# Main.net
KiCad netlist of a schematic drawn in Altium Designer
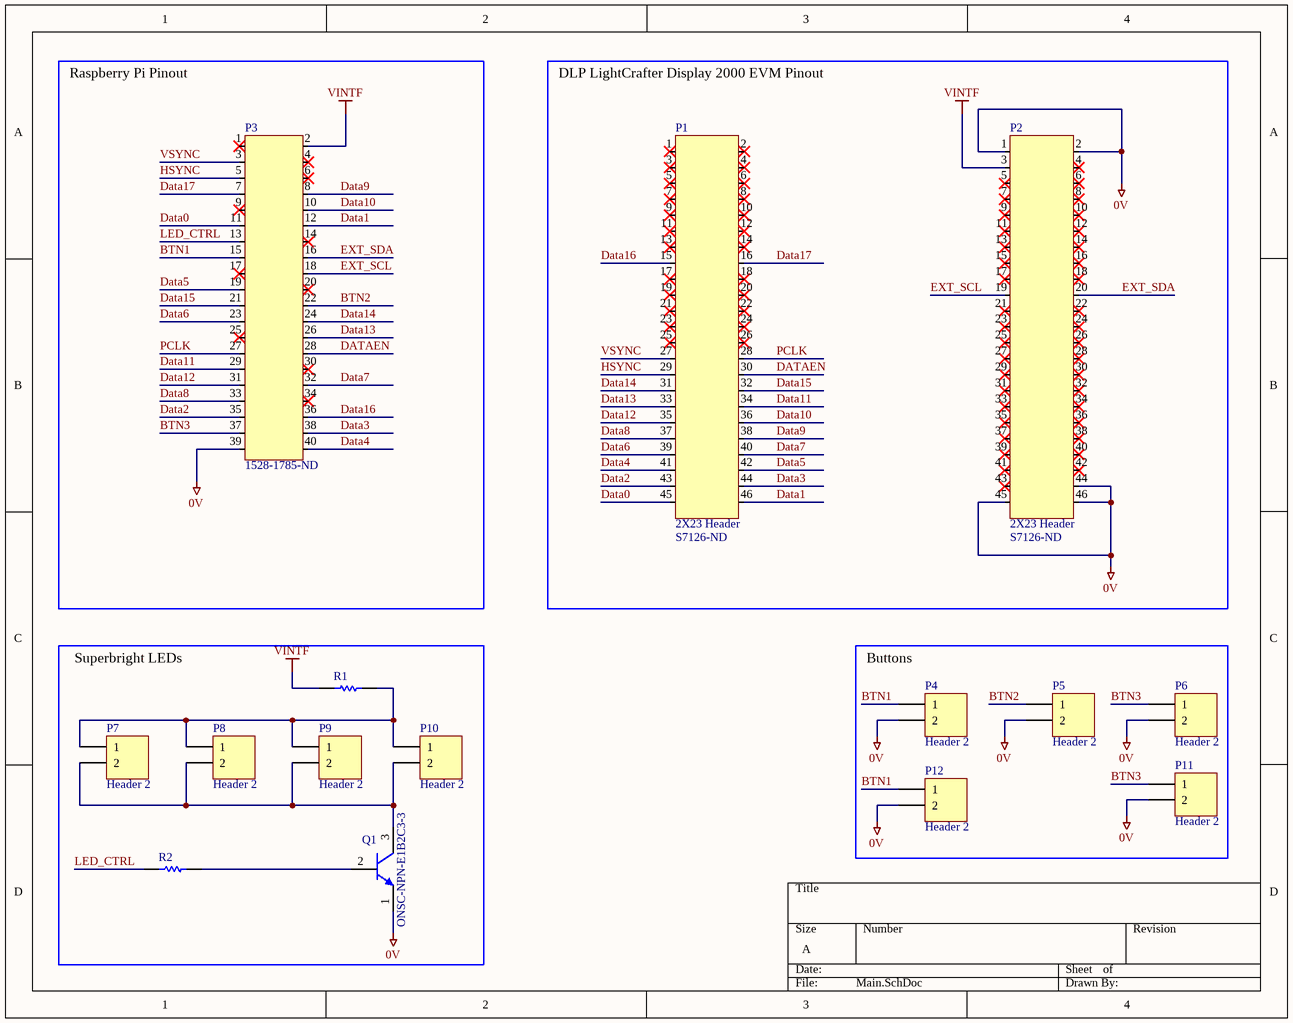
[diagram p0: Main.SchDoc]

(export (version "E")
  (design (tool "Eeschema 10.0.6"))
  (components
    (comp (ref "P1")
      (value "2X23 Header")
      (footprint "2X23 hEADER")
      (fields
        (field (name "MANUFACTURER") "Sullins")
        (field (name "MANUFACTURER PART NUMBER") "PPPC232LFBN-RC")
        (field (name "SUPPLIER PART NUMBER 1") "S7126-ND")
      )
      (libsource (lib "BikeHUD") (part "PPPC232LFBN-RC"))
    )
    (comp (ref "P2")
      (value "2X23 Header")
      (footprint "2X23 hEADER")
      (fields
        (field (name "MANUFACTURER") "Sullins")
        (field (name "MANUFACTURER PART NUMBER") "PPPC232LFBN-RC")
        (field (name "SUPPLIER PART NUMBER 1") "S7126-ND")
      )
      (libsource (lib "BikeHUD") (part "PPPC232LFBN-RC"))
    )
    (comp (ref "P3")
      (value "2x20 Header")
      (footprint "2222")
      (description "GPIO FEMALE HEADER RASPBERRY PI")
      (fields
        (field (name "MANUFACTURER") "Adafruit Industries")
        (field (name "MANUFACTURER PART NUMBER") "2222")
        (field (name "SUPPLIER PART NUMBER 1") "1528-1785-ND")
      )
      (libsource (lib "BikeHUD") (part "2222"))
    )
    (comp (ref "P4")
      (value "Header 2")
      (footprint "HDR1X2")
      (description "Header, 2-Pin")
      (fields (field (name "PUBLISHER") "Altium Limited"))
      (libsource (lib "BikeHUD") (part "Header 2"))
    )
    (comp (ref "P5")
      (value "Header 2")
      (footprint "HDR1X2")
      (description "Header, 2-Pin")
      (fields (field (name "PUBLISHER") "Altium Limited"))
      (libsource (lib "BikeHUD") (part "Header 2"))
    )
    (comp (ref "P6")
      (value "Header 2")
      (footprint "HDR1X2")
      (description "Header, 2-Pin")
      (fields (field (name "PUBLISHER") "Altium Limited"))
      (libsource (lib "BikeHUD") (part "Header 2"))
    )
    (comp (ref "P7")
      (value "Header 2")
      (footprint "HDR1X2")
      (description "Header, 2-Pin")
      (fields (field (name "PUBLISHER") "Altium Limited"))
      (libsource (lib "BikeHUD") (part "Header 2"))
    )
    (comp (ref "P8")
      (value "Header 2")
      (footprint "HDR1X2")
      (description "Header, 2-Pin")
      (fields (field (name "PUBLISHER") "Altium Limited"))
      (libsource (lib "BikeHUD") (part "Header 2"))
    )
    (comp (ref "P9")
      (value "Header 2")
      (footprint "HDR1X2")
      (description "Header, 2-Pin")
      (fields (field (name "PUBLISHER") "Altium Limited"))
      (libsource (lib "BikeHUD") (part "Header 2"))
    )
    (comp (ref "P10")
      (value "Header 2")
      (footprint "HDR1X2")
      (description "Header, 2-Pin")
      (fields (field (name "PUBLISHER") "Altium Limited"))
      (libsource (lib "BikeHUD") (part "Header 2"))
    )
    (comp (ref "P11")
      (value "Header 2")
      (footprint "HDR1X2")
      (description "Header, 2-Pin")
      (fields (field (name "PUBLISHER") "Altium Limited"))
      (libsource (lib "BikeHUD") (part "Header 2"))
    )
    (comp (ref "P12")
      (value "Header 2")
      (footprint "HDR1X2")
      (description "Header, 2-Pin")
      (fields (field (name "PUBLISHER") "Altium Limited"))
      (libsource (lib "BikeHUD") (part "Header 2"))
    )
    (comp (ref "Q1")
      (value "ONSC-NPN-E1B2C3-3")
      (footprint "ONSC-TO-92-3-29-11")
      (libsource (lib "BikeHUD") (part "ONSC-NPN-E1B2C3-3"))
    )
    (comp (ref "R1")
      (value "Res1")
      (footprint "AXIAL-0.3")
      (description "Resistor")
      (fields (field (name "PUBLISHER") "Altium Limited"))
      (libsource (lib "BikeHUD") (part "Res1"))
    )
    (comp (ref "R2")
      (value "Res1")
      (footprint "AXIAL-0.3")
      (description "Resistor")
      (fields (field (name "PUBLISHER") "Altium Limited"))
      (libsource (lib "BikeHUD") (part "Res1"))
    )
  )
  (nets
    (net (code "1") (name "/BTN1") (class "Default")
      (node (ref "P12") (pin "1") (pinfunction "1_1") (pintype "passive"))
      (node (ref "P3") (pin "15") (pinfunction "15_15") (pintype "passive"))
      (node (ref "P4") (pin "1") (pinfunction "1_1") (pintype "passive"))
    )
    (net (code "2") (name "/BTN2") (class "Default")
      (node (ref "P3") (pin "22") (pinfunction "22_22") (pintype "passive"))
      (node (ref "P5") (pin "1") (pinfunction "1_1") (pintype "passive"))
    )
    (net (code "3") (name "/BTN3") (class "Default")
      (node (ref "P11") (pin "1") (pinfunction "1_1") (pintype "passive"))
      (node (ref "P3") (pin "37") (pinfunction "37_37") (pintype "passive"))
      (node (ref "P6") (pin "1") (pinfunction "1_1") (pintype "passive"))
    )
    (net (code "4") (name "/DATAEN") (class "Default")
      (node (ref "P1") (pin "30") (pinfunction "30_30") (pintype "passive"))
      (node (ref "P3") (pin "28") (pinfunction "28_28") (pintype "passive"))
    )
    (net (code "5") (name "/Data0") (class "Default")
      (node (ref "P1") (pin "45") (pinfunction "45_45") (pintype "passive"))
      (node (ref "P3") (pin "11") (pinfunction "11_11") (pintype "passive"))
    )
    (net (code "6") (name "/Data1") (class "Default")
      (node (ref "P1") (pin "46") (pinfunction "46_46") (pintype "passive"))
      (node (ref "P3") (pin "12") (pinfunction "12_12") (pintype "passive"))
    )
    (net (code "7") (name "/Data2") (class "Default")
      (node (ref "P1") (pin "43") (pinfunction "43_43") (pintype "passive"))
      (node (ref "P3") (pin "35") (pinfunction "35_35") (pintype "passive"))
    )
    (net (code "8") (name "/Data3") (class "Default")
      (node (ref "P1") (pin "44") (pinfunction "44_44") (pintype "passive"))
      (node (ref "P3") (pin "38") (pinfunction "38_38") (pintype "passive"))
    )
    (net (code "9") (name "/Data4") (class "Default")
      (node (ref "P1") (pin "41") (pinfunction "41_41") (pintype "passive"))
      (node (ref "P3") (pin "40") (pinfunction "40_40") (pintype "passive"))
    )
    (net (code "10") (name "/Data5") (class "Default")
      (node (ref "P1") (pin "42") (pinfunction "42_42") (pintype "passive"))
      (node (ref "P3") (pin "19") (pinfunction "19_19") (pintype "passive"))
    )
    (net (code "11") (name "/Data6") (class "Default")
      (node (ref "P1") (pin "39") (pinfunction "39_39") (pintype "passive"))
      (node (ref "P3") (pin "23") (pinfunction "23_23") (pintype "passive"))
    )
    (net (code "12") (name "/Data7") (class "Default")
      (node (ref "P1") (pin "40") (pinfunction "40_40") (pintype "passive"))
      (node (ref "P3") (pin "32") (pinfunction "32_32") (pintype "passive"))
    )
    (net (code "13") (name "/Data8") (class "Default")
      (node (ref "P1") (pin "37") (pinfunction "37_37") (pintype "passive"))
      (node (ref "P3") (pin "33") (pinfunction "33_33") (pintype "passive"))
    )
    (net (code "14") (name "/Data9") (class "Default")
      (node (ref "P1") (pin "38") (pinfunction "38_38") (pintype "passive"))
      (node (ref "P3") (pin "8") (pinfunction "8_8") (pintype "passive"))
    )
    (net (code "15") (name "/Data10") (class "Default")
      (node (ref "P1") (pin "36") (pinfunction "36_36") (pintype "passive"))
      (node (ref "P3") (pin "10") (pinfunction "10_10") (pintype "passive"))
    )
    (net (code "16") (name "/Data11") (class "Default")
      (node (ref "P1") (pin "34") (pinfunction "34_34") (pintype "passive"))
      (node (ref "P3") (pin "29") (pinfunction "29_29") (pintype "passive"))
    )
    (net (code "17") (name "/Data12") (class "Default")
      (node (ref "P1") (pin "35") (pinfunction "35_35") (pintype "passive"))
      (node (ref "P3") (pin "31") (pinfunction "31_31") (pintype "passive"))
    )
    (net (code "18") (name "/Data13") (class "Default")
      (node (ref "P1") (pin "33") (pinfunction "33_33") (pintype "passive"))
      (node (ref "P3") (pin "26") (pinfunction "26_26") (pintype "passive"))
    )
    (net (code "19") (name "/Data14") (class "Default")
      (node (ref "P1") (pin "31") (pinfunction "31_31") (pintype "passive"))
      (node (ref "P3") (pin "24") (pinfunction "24_24") (pintype "passive"))
    )
    (net (code "20") (name "/Data15") (class "Default")
      (node (ref "P1") (pin "32") (pinfunction "32_32") (pintype "passive"))
      (node (ref "P3") (pin "21") (pinfunction "21_21") (pintype "passive"))
    )
    (net (code "21") (name "/Data16") (class "Default")
      (node (ref "P1") (pin "15") (pinfunction "15_15") (pintype "passive"))
      (node (ref "P3") (pin "36") (pinfunction "36_36") (pintype "passive"))
    )
    (net (code "22") (name "/Data17") (class "Default")
      (node (ref "P1") (pin "16") (pinfunction "16_16") (pintype "passive"))
      (node (ref "P3") (pin "7") (pinfunction "7_7") (pintype "passive"))
    )
    (net (code "23") (name "/EXT_SCL") (class "Default")
      (node (ref "P2") (pin "19") (pinfunction "19_19") (pintype "passive"))
      (node (ref "P3") (pin "18") (pinfunction "_18_18") (pintype "passive"))
    )
    (net (code "24") (name "/EXT_SDA") (class "Default")
      (node (ref "P2") (pin "20") (pinfunction "20_20") (pintype "passive"))
      (node (ref "P3") (pin "16") (pinfunction "16_16") (pintype "passive"))
    )
    (net (code "25") (name "/HSYNC") (class "Default")
      (node (ref "P1") (pin "29") (pinfunction "29_29") (pintype "passive"))
      (node (ref "P3") (pin "5") (pinfunction "5_5") (pintype "passive"))
    )
    (net (code "26") (name "/LED_CTRL") (class "Default")
      (node (ref "P3") (pin "13") (pinfunction "13_13") (pintype "passive"))
      (node (ref "R2") (pin "1") (pinfunction "1_1") (pintype "passive"))
    )
    (net (code "27") (name "/PCLK") (class "Default")
      (node (ref "P1") (pin "28") (pinfunction "28_28") (pintype "passive"))
      (node (ref "P3") (pin "27") (pinfunction "27_27") (pintype "passive"))
    )
    (net (code "28") (name "/VSYNC") (class "Default")
      (node (ref "P1") (pin "27") (pinfunction "27_27") (pintype "passive"))
      (node (ref "P3") (pin "3") (pinfunction "3_3") (pintype "passive"))
    )
    (net (code "29") (name "0V") (class "Default")
      (node (ref "P11") (pin "2") (pinfunction "2_2") (pintype "passive"))
      (node (ref "P12") (pin "2") (pinfunction "2_2") (pintype "passive"))
      (node (ref "P2") (pin "1") (pinfunction "1_1") (pintype "passive"))
      (node (ref "P2") (pin "2") (pinfunction "2_2") (pintype "passive"))
      (node (ref "P2") (pin "44") (pinfunction "44_44") (pintype "passive"))
      (node (ref "P2") (pin "45") (pinfunction "45_45") (pintype "passive"))
      (node (ref "P2") (pin "46") (pinfunction "46_46") (pintype "passive"))
      (node (ref "P3") (pin "39") (pinfunction "39_39") (pintype "passive"))
      (node (ref "P4") (pin "2") (pinfunction "2_2") (pintype "passive"))
      (node (ref "P5") (pin "2") (pinfunction "2_2") (pintype "passive"))
      (node (ref "P6") (pin "2") (pinfunction "2_2") (pintype "passive"))
      (node (ref "Q1") (pin "1") (pinfunction "E_1") (pintype "passive"))
    )
    (net (code "30") (name "Net-(P10-Pad1)") (class "Default")
      (node (ref "P10") (pin "1") (pinfunction "1_1") (pintype "passive"))
      (node (ref "P7") (pin "1") (pinfunction "1_1") (pintype "passive"))
      (node (ref "P8") (pin "1") (pinfunction "1_1") (pintype "passive"))
      (node (ref "P9") (pin "1") (pinfunction "1_1") (pintype "passive"))
      (node (ref "R1") (pin "2") (pinfunction "2_2") (pintype "passive"))
    )
    (net (code "31") (name "Net-(Q1-B)") (class "Default")
      (node (ref "Q1") (pin "2") (pinfunction "B_2") (pintype "passive"))
      (node (ref "R2") (pin "2") (pinfunction "2_2") (pintype "passive"))
    )
    (net (code "32") (name "Net-(Q1-C)") (class "Default")
      (node (ref "P10") (pin "2") (pinfunction "2_2") (pintype "passive"))
      (node (ref "P7") (pin "2") (pinfunction "2_2") (pintype "passive"))
      (node (ref "P8") (pin "2") (pinfunction "2_2") (pintype "passive"))
      (node (ref "P9") (pin "2") (pinfunction "2_2") (pintype "passive"))
      (node (ref "Q1") (pin "3") (pinfunction "C_3") (pintype "passive"))
    )
    (net (code "33") (name "VINTF") (class "Default")
      (node (ref "P2") (pin "3") (pinfunction "3_3") (pintype "passive"))
      (node (ref "P3") (pin "2") (pinfunction "2_2") (pintype "passive"))
      (node (ref "R1") (pin "1") (pinfunction "1_1") (pintype "passive"))
    )
    (net (code "34") (name "unconnected-(P1-Pad1)") (class "Default")
      (node (ref "P1") (pin "1") (pinfunction "1_1") (pintype "passive+no_connect"))
    )
    (net (code "35") (name "unconnected-(P1-Pad2)") (class "Default")
      (node (ref "P1") (pin "2") (pinfunction "2_2") (pintype "passive+no_connect"))
    )
    (net (code "36") (name "unconnected-(P1-Pad3)") (class "Default")
      (node (ref "P1") (pin "3") (pinfunction "3_3") (pintype "passive+no_connect"))
    )
    (net (code "37") (name "unconnected-(P1-Pad4)") (class "Default")
      (node (ref "P1") (pin "4") (pinfunction "4_4") (pintype "passive+no_connect"))
    )
    (net (code "38") (name "unconnected-(P1-Pad5)") (class "Default")
      (node (ref "P1") (pin "5") (pinfunction "5_5") (pintype "passive+no_connect"))
    )
    (net (code "39") (name "unconnected-(P1-Pad6)") (class "Default")
      (node (ref "P1") (pin "6") (pinfunction "6_6") (pintype "passive+no_connect"))
    )
    (net (code "40") (name "unconnected-(P1-Pad7)") (class "Default")
      (node (ref "P1") (pin "7") (pinfunction "7_7") (pintype "passive+no_connect"))
    )
    (net (code "41") (name "unconnected-(P1-Pad8)") (class "Default")
      (node (ref "P1") (pin "8") (pinfunction "8_8") (pintype "passive+no_connect"))
    )
    (net (code "42") (name "unconnected-(P1-Pad9)") (class "Default")
      (node (ref "P1") (pin "9") (pinfunction "9_9") (pintype "passive+no_connect"))
    )
    (net (code "43") (name "unconnected-(P1-Pad10)") (class "Default")
      (node (ref "P1") (pin "10") (pinfunction "10_10") (pintype "passive+no_connect"))
    )
    (net (code "44") (name "unconnected-(P1-Pad11)") (class "Default")
      (node (ref "P1") (pin "11") (pinfunction "11_11") (pintype "passive+no_connect"))
    )
    (net (code "45") (name "unconnected-(P1-Pad12)") (class "Default")
      (node (ref "P1") (pin "12") (pinfunction "12_12") (pintype "passive+no_connect"))
    )
    (net (code "46") (name "unconnected-(P1-Pad13)") (class "Default")
      (node (ref "P1") (pin "13") (pinfunction "13_13") (pintype "passive+no_connect"))
    )
    (net (code "47") (name "unconnected-(P1-Pad14)") (class "Default")
      (node (ref "P1") (pin "14") (pinfunction "14_14") (pintype "passive+no_connect"))
    )
    (net (code "48") (name "unconnected-(P1-Pad17)") (class "Default")
      (node (ref "P1") (pin "17") (pinfunction "17_17") (pintype "passive+no_connect"))
    )
    (net (code "49") (name "unconnected-(P1-Pad18)") (class "Default")
      (node (ref "P1") (pin "18") (pinfunction "18_18") (pintype "passive+no_connect"))
    )
    (net (code "50") (name "unconnected-(P1-Pad19)") (class "Default")
      (node (ref "P1") (pin "19") (pinfunction "19_19") (pintype "passive+no_connect"))
    )
    (net (code "51") (name "unconnected-(P1-Pad20)") (class "Default")
      (node (ref "P1") (pin "20") (pinfunction "20_20") (pintype "passive+no_connect"))
    )
    (net (code "52") (name "unconnected-(P1-Pad21)") (class "Default")
      (node (ref "P1") (pin "21") (pinfunction "21_21") (pintype "passive+no_connect"))
    )
    (net (code "53") (name "unconnected-(P1-Pad22)") (class "Default")
      (node (ref "P1") (pin "22") (pinfunction "22_22") (pintype "passive+no_connect"))
    )
    (net (code "54") (name "unconnected-(P1-Pad23)") (class "Default")
      (node (ref "P1") (pin "23") (pinfunction "23_23") (pintype "passive+no_connect"))
    )
    (net (code "55") (name "unconnected-(P1-Pad24)") (class "Default")
      (node (ref "P1") (pin "24") (pinfunction "24_24") (pintype "passive+no_connect"))
    )
    (net (code "56") (name "unconnected-(P1-Pad25)") (class "Default")
      (node (ref "P1") (pin "25") (pinfunction "25_25") (pintype "passive+no_connect"))
    )
    (net (code "57") (name "unconnected-(P1-Pad26)") (class "Default")
      (node (ref "P1") (pin "26") (pinfunction "26_26") (pintype "passive+no_connect"))
    )
    (net (code "58") (name "unconnected-(P2-Pad4)") (class "Default")
      (node (ref "P2") (pin "4") (pinfunction "4_4") (pintype "passive+no_connect"))
    )
    (net (code "59") (name "unconnected-(P2-Pad5)") (class "Default")
      (node (ref "P2") (pin "5") (pinfunction "5_5") (pintype "passive+no_connect"))
    )
    (net (code "60") (name "unconnected-(P2-Pad6)") (class "Default")
      (node (ref "P2") (pin "6") (pinfunction "6_6") (pintype "passive+no_connect"))
    )
    (net (code "61") (name "unconnected-(P2-Pad7)") (class "Default")
      (node (ref "P2") (pin "7") (pinfunction "7_7") (pintype "passive+no_connect"))
    )
    (net (code "62") (name "unconnected-(P2-Pad8)") (class "Default")
      (node (ref "P2") (pin "8") (pinfunction "8_8") (pintype "passive+no_connect"))
    )
    (net (code "63") (name "unconnected-(P2-Pad9)") (class "Default")
      (node (ref "P2") (pin "9") (pinfunction "9_9") (pintype "passive+no_connect"))
    )
    (net (code "64") (name "unconnected-(P2-Pad10)") (class "Default")
      (node (ref "P2") (pin "10") (pinfunction "10_10") (pintype "passive+no_connect"))
    )
    (net (code "65") (name "unconnected-(P2-Pad11)") (class "Default")
      (node (ref "P2") (pin "11") (pinfunction "11_11") (pintype "passive+no_connect"))
    )
    (net (code "66") (name "unconnected-(P2-Pad12)") (class "Default")
      (node (ref "P2") (pin "12") (pinfunction "12_12") (pintype "passive+no_connect"))
    )
    (net (code "67") (name "unconnected-(P2-Pad13)") (class "Default")
      (node (ref "P2") (pin "13") (pinfunction "13_13") (pintype "passive+no_connect"))
    )
    (net (code "68") (name "unconnected-(P2-Pad14)") (class "Default")
      (node (ref "P2") (pin "14") (pinfunction "14_14") (pintype "passive+no_connect"))
    )
    (net (code "69") (name "unconnected-(P2-Pad15)") (class "Default")
      (node (ref "P2") (pin "15") (pinfunction "15_15") (pintype "passive+no_connect"))
    )
    (net (code "70") (name "unconnected-(P2-Pad16)") (class "Default")
      (node (ref "P2") (pin "16") (pinfunction "16_16") (pintype "passive+no_connect"))
    )
    (net (code "71") (name "unconnected-(P2-Pad17)") (class "Default")
      (node (ref "P2") (pin "17") (pinfunction "17_17") (pintype "passive+no_connect"))
    )
    (net (code "72") (name "unconnected-(P2-Pad18)") (class "Default")
      (node (ref "P2") (pin "18") (pinfunction "18_18") (pintype "passive+no_connect"))
    )
    (net (code "73") (name "unconnected-(P2-Pad21)") (class "Default")
      (node (ref "P2") (pin "21") (pinfunction "21_21") (pintype "passive+no_connect"))
    )
    (net (code "74") (name "unconnected-(P2-Pad22)") (class "Default")
      (node (ref "P2") (pin "22") (pinfunction "22_22") (pintype "passive+no_connect"))
    )
    (net (code "75") (name "unconnected-(P2-Pad23)") (class "Default")
      (node (ref "P2") (pin "23") (pinfunction "23_23") (pintype "passive+no_connect"))
    )
    (net (code "76") (name "unconnected-(P2-Pad24)") (class "Default")
      (node (ref "P2") (pin "24") (pinfunction "24_24") (pintype "passive+no_connect"))
    )
    (net (code "77") (name "unconnected-(P2-Pad25)") (class "Default")
      (node (ref "P2") (pin "25") (pinfunction "25_25") (pintype "passive+no_connect"))
    )
    (net (code "78") (name "unconnected-(P2-Pad26)") (class "Default")
      (node (ref "P2") (pin "26") (pinfunction "26_26") (pintype "passive+no_connect"))
    )
    (net (code "79") (name "unconnected-(P2-Pad27)") (class "Default")
      (node (ref "P2") (pin "27") (pinfunction "27_27") (pintype "passive+no_connect"))
    )
    (net (code "80") (name "unconnected-(P2-Pad28)") (class "Default")
      (node (ref "P2") (pin "28") (pinfunction "28_28") (pintype "passive+no_connect"))
    )
    (net (code "81") (name "unconnected-(P2-Pad29)") (class "Default")
      (node (ref "P2") (pin "29") (pinfunction "29_29") (pintype "passive+no_connect"))
    )
    (net (code "82") (name "unconnected-(P2-Pad30)") (class "Default")
      (node (ref "P2") (pin "30") (pinfunction "30_30") (pintype "passive+no_connect"))
    )
    (net (code "83") (name "unconnected-(P2-Pad31)") (class "Default")
      (node (ref "P2") (pin "31") (pinfunction "31_31") (pintype "passive+no_connect"))
    )
    (net (code "84") (name "unconnected-(P2-Pad32)") (class "Default")
      (node (ref "P2") (pin "32") (pinfunction "32_32") (pintype "passive+no_connect"))
    )
    (net (code "85") (name "unconnected-(P2-Pad33)") (class "Default")
      (node (ref "P2") (pin "33") (pinfunction "33_33") (pintype "passive+no_connect"))
    )
    (net (code "86") (name "unconnected-(P2-Pad34)") (class "Default")
      (node (ref "P2") (pin "34") (pinfunction "34_34") (pintype "passive+no_connect"))
    )
    (net (code "87") (name "unconnected-(P2-Pad35)") (class "Default")
      (node (ref "P2") (pin "35") (pinfunction "35_35") (pintype "passive+no_connect"))
    )
    (net (code "88") (name "unconnected-(P2-Pad36)") (class "Default")
      (node (ref "P2") (pin "36") (pinfunction "36_36") (pintype "passive+no_connect"))
    )
    (net (code "89") (name "unconnected-(P2-Pad37)") (class "Default")
      (node (ref "P2") (pin "37") (pinfunction "37_37") (pintype "passive+no_connect"))
    )
    (net (code "90") (name "unconnected-(P2-Pad38)") (class "Default")
      (node (ref "P2") (pin "38") (pinfunction "38_38") (pintype "passive+no_connect"))
    )
    (net (code "91") (name "unconnected-(P2-Pad39)") (class "Default")
      (node (ref "P2") (pin "39") (pinfunction "39_39") (pintype "passive+no_connect"))
    )
    (net (code "92") (name "unconnected-(P2-Pad40)") (class "Default")
      (node (ref "P2") (pin "40") (pinfunction "40_40") (pintype "passive+no_connect"))
    )
    (net (code "93") (name "unconnected-(P2-Pad41)") (class "Default")
      (node (ref "P2") (pin "41") (pinfunction "41_41") (pintype "passive+no_connect"))
    )
    (net (code "94") (name "unconnected-(P2-Pad42)") (class "Default")
      (node (ref "P2") (pin "42") (pinfunction "42_42") (pintype "passive+no_connect"))
    )
    (net (code "95") (name "unconnected-(P2-Pad43)") (class "Default")
      (node (ref "P2") (pin "43") (pinfunction "43_43") (pintype "passive+no_connect"))
    )
    (net (code "96") (name "unconnected-(P3-Pad1)") (class "Default")
      (node (ref "P3") (pin "1") (pinfunction "1_1") (pintype "passive+no_connect"))
    )
    (net (code "97") (name "unconnected-(P3-Pad4)") (class "Default")
      (node (ref "P3") (pin "4") (pinfunction "4_4") (pintype "passive+no_connect"))
    )
    (net (code "98") (name "unconnected-(P3-Pad6)") (class "Default")
      (node (ref "P3") (pin "6") (pinfunction "6_6") (pintype "passive+no_connect"))
    )
    (net (code "99") (name "unconnected-(P3-Pad9)") (class "Default")
      (node (ref "P3") (pin "9") (pinfunction "9_9") (pintype "passive+no_connect"))
    )
    (net (code "100") (name "unconnected-(P3-Pad14)") (class "Default")
      (node (ref "P3") (pin "14") (pinfunction "14_14") (pintype "passive+no_connect"))
    )
    (net (code "101") (name "unconnected-(P3-Pad17)") (class "Default")
      (node (ref "P3") (pin "17") (pinfunction "17_17") (pintype "passive+no_connect"))
    )
    (net (code "102") (name "unconnected-(P3-Pad20)") (class "Default")
      (node (ref "P3") (pin "20") (pinfunction "20_20") (pintype "passive+no_connect"))
    )
    (net (code "103") (name "unconnected-(P3-Pad25)") (class "Default")
      (node (ref "P3") (pin "25") (pinfunction "25_25") (pintype "passive+no_connect"))
    )
    (net (code "104") (name "unconnected-(P3-Pad30)") (class "Default")
      (node (ref "P3") (pin "30") (pinfunction "30_30") (pintype "passive+no_connect"))
    )
    (net (code "105") (name "unconnected-(P3-Pad34)") (class "Default")
      (node (ref "P3") (pin "34") (pinfunction "34_34") (pintype "passive+no_connect"))
    )
  )
)
